# schematic.net
KiCad netlist of a schematic drawn in EAGLE
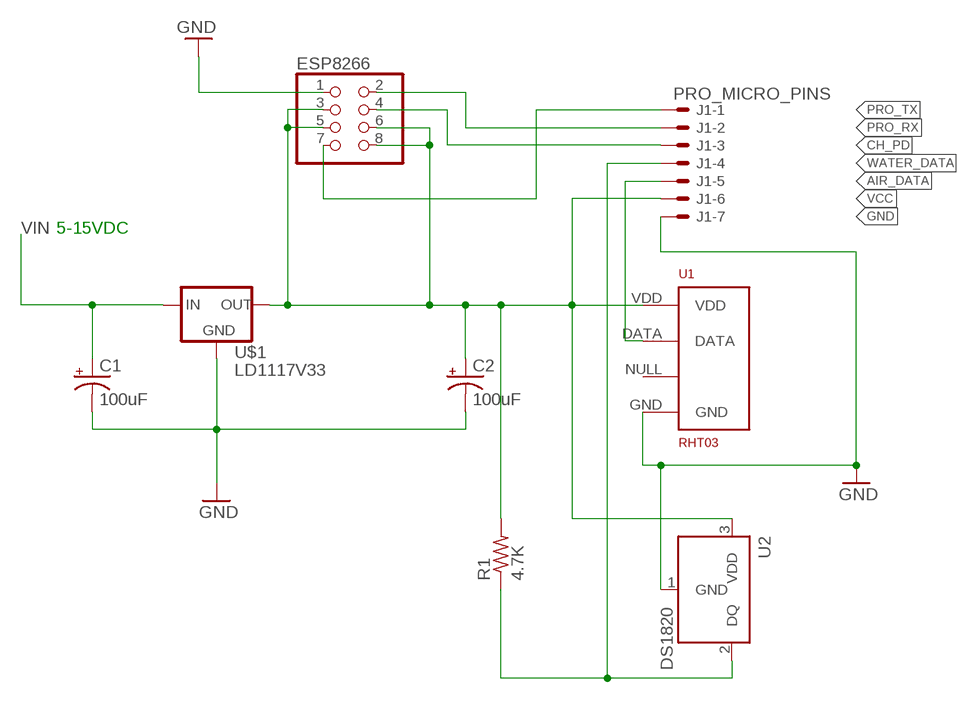
[diagram p0: schematic, sheet 1]

(export (version "E")
  (design (tool "Eeschema 10.0.6"))
  (components
    (comp (ref "C1")
      (value "100uF")
      (footprint "eagle-import:CPOL-RADIAL-100UF-25V")
      (libsource (lib "eagle-import") (part "100UF-25V-20%(PTH)"))
    )
    (comp (ref "C2")
      (value "100uF")
      (footprint "eagle-import:CPOL-RADIAL-100UF-25V")
      (libsource (lib "eagle-import") (part "100UF-25V-20%(PTH)"))
    )
    (comp (ref "ESP8266")
      (value "PINHD-2X4")
      (footprint "eagle-import:2X04")
      (libsource (lib "eagle-import") (part "PINHD-2X4"))
    )
    (comp (ref "J1")
      (value "PRO_MICRO_PINS")
      (footprint "eagle-import:22-23-2071")
      (fields (field (name "MF") "MOLEX") (field (name "MPN") "22-23-2071"))
      (libsource (lib "eagle-import") (part "22-23-2071"))
    )
    (comp (ref "R1")
      (value "4.7K")
      (footprint "eagle-import:0207_10")
      (libsource (lib "eagle-import") (part "R-US_0207/10"))
    )
    (comp (ref "U$1")
      (value "LD1117V33")
      (footprint "eagle-import:78XXL")
      (libsource (lib "eagle-import") (part "V_REG_LD1117VXX"))
    )
    (comp (ref "U1")
      (value "RHT03")
      (footprint "eagle-import:RHT03_DHT-22")
      (libsource (lib "eagle-import") (part "RHT03_DHT-22_AM2302"))
    )
    (comp (ref "U2")
      (value "DS1820")
      (footprint "eagle-import:TO-92")
      (libsource (lib "eagle-import") (part "DS1820"))
    )
  )
  (nets
    (net (code "1") (name "/VIN") (class "Default")
      (node (ref "C1") (pin "1") (pinfunction "+_1") (pintype "passive"))
      (node (ref "U$1") (pin "OUT") (pinfunction "IN_OUT") (pintype "input"))
    )
    (net (code "2") (name "AIR_DATA") (class "Default")
      (node (ref "J1") (pin "5") (pinfunction "S_5") (pintype "passive"))
      (node (ref "U1") (pin "DATA") (pinfunction "DATA_DATA") (pintype "bidirectional"))
    )
    (net (code "3") (name "CH_PD") (class "Default")
      (node (ref "ESP8266") (pin "4") (pinfunction "4_4") (pintype "passive"))
      (node (ref "J1") (pin "3") (pinfunction "S_3") (pintype "passive"))
    )
    (net (code "4") (name "GND") (class "Default")
      (node (ref "C1") (pin "2") (pinfunction "-_2") (pintype "passive"))
      (node (ref "C2") (pin "2") (pinfunction "-_2") (pintype "passive"))
      (node (ref "ESP8266") (pin "1") (pinfunction "1_1") (pintype "passive"))
      (node (ref "J1") (pin "7") (pinfunction "S_7") (pintype "passive"))
      (node (ref "U$1") (pin "IN") (pinfunction "GND_IN") (pintype "input"))
      (node (ref "U1") (pin "GND") (pinfunction "GND_GND") (pintype "power_in"))
      (node (ref "U2") (pin "1") (pinfunction "GND_1") (pintype "power_in"))
    )
    (net (code "5") (name "PRO_RX") (class "Default")
      (node (ref "ESP8266") (pin "2") (pinfunction "2_2") (pintype "passive"))
      (node (ref "J1") (pin "2") (pinfunction "S_2") (pintype "passive"))
    )
    (net (code "6") (name "PRO_TX") (class "Default")
      (node (ref "ESP8266") (pin "7") (pinfunction "7_7") (pintype "passive"))
      (node (ref "J1") (pin "1") (pinfunction "S_1") (pintype "passive"))
    )
    (net (code "7") (name "VCC") (class "Default")
      (node (ref "C2") (pin "1") (pinfunction "+_1") (pintype "passive"))
      (node (ref "ESP8266") (pin "3") (pinfunction "3_3") (pintype "passive"))
      (node (ref "ESP8266") (pin "5") (pinfunction "5_5") (pintype "passive"))
      (node (ref "ESP8266") (pin "6") (pinfunction "6_6") (pintype "passive"))
      (node (ref "ESP8266") (pin "8") (pinfunction "8_8") (pintype "passive"))
      (node (ref "J1") (pin "6") (pinfunction "S_6") (pintype "passive"))
      (node (ref "R1") (pin "2") (pinfunction "2_2") (pintype "passive"))
      (node (ref "U$1") (pin "GND") (pinfunction "OUT_GND") (pintype "passive"))
      (node (ref "U1") (pin "VDD") (pinfunction "VDD_VDD") (pintype "power_in"))
      (node (ref "U2") (pin "3") (pinfunction "VDD_3") (pintype "input"))
    )
    (net (code "8") (name "WATER_DATA") (class "Default")
      (node (ref "J1") (pin "4") (pinfunction "S_4") (pintype "passive"))
      (node (ref "R1") (pin "1") (pinfunction "1_1") (pintype "passive"))
      (node (ref "U2") (pin "2") (pinfunction "DQ_2") (pintype "output"))
    )
    (net (code "9") (name "unconnected-(U1-PadNULL)") (class "Default")
      (node (ref "U1") (pin "NULL") (pinfunction "NULL_NULL") (pintype "no_connect"))
    )
  )
)
